# JCarlos_e_Renato.net
KiCad netlist of a schematic drawn in EAGLE
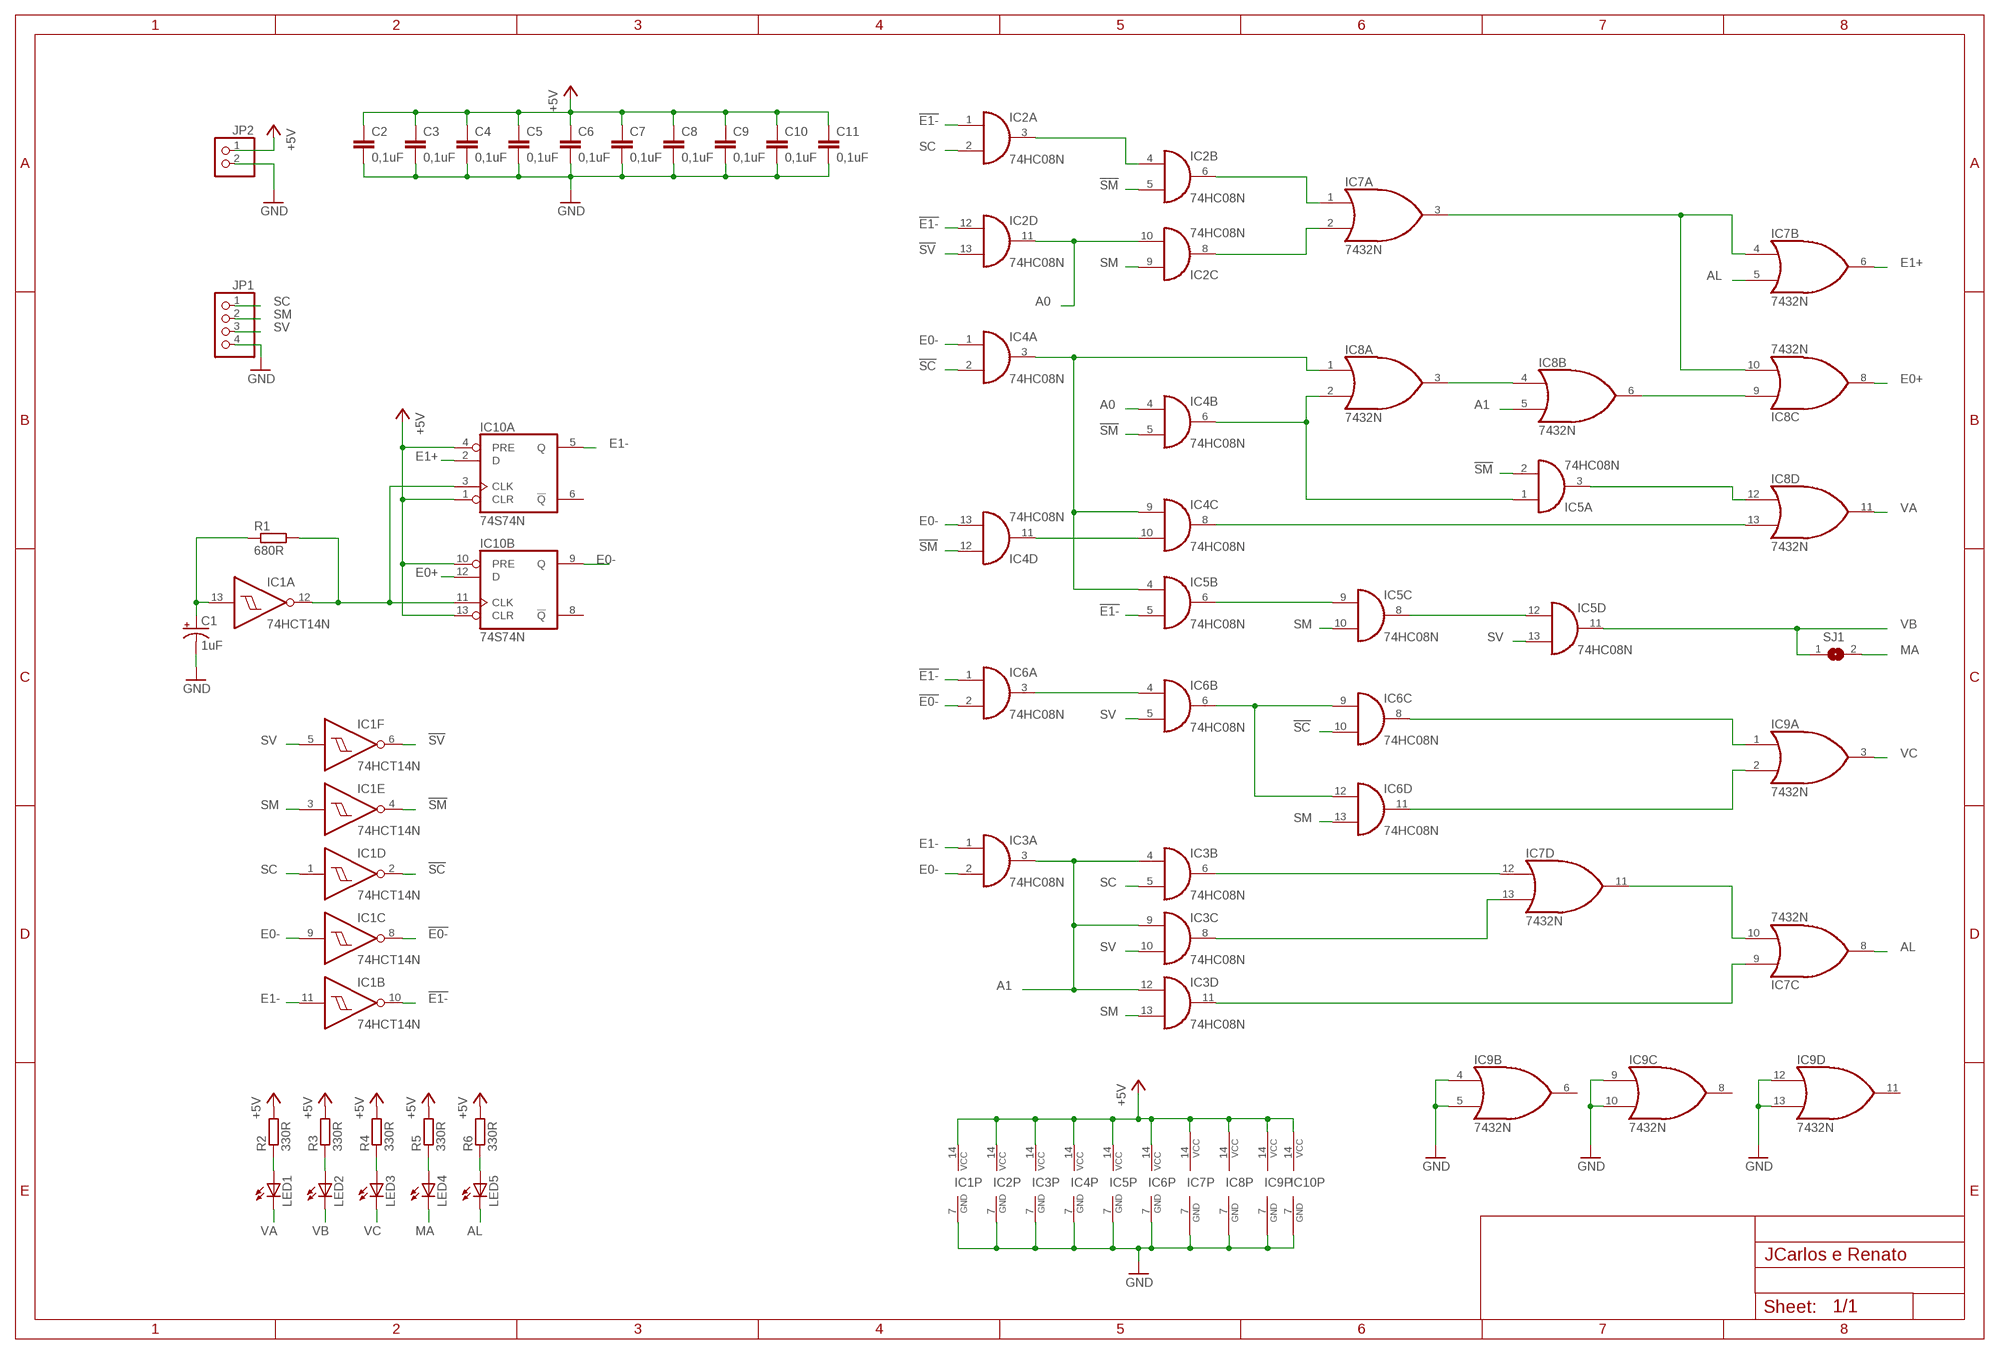
[diagram p0: schematic, sheet 1]

(export (version "E")
  (design (tool "Eeschema 10.0.6"))
  (components
    (comp (ref "C1")
      (value "1uF")
      (footprint "eagle-import:E5-6")
      (libsource (lib "eagle-import") (part "CPOL-USE5-6"))
    )
    (comp (ref "C2")
      (value "0,1uF")
      (footprint "eagle-import:C050-025X075")
      (libsource (lib "eagle-import") (part "C-EU050-025X075"))
    )
    (comp (ref "C3")
      (value "0,1uF")
      (footprint "eagle-import:C050-025X075")
      (libsource (lib "eagle-import") (part "C-EU050-025X075"))
    )
    (comp (ref "C4")
      (value "0,1uF")
      (footprint "eagle-import:C050-025X075")
      (libsource (lib "eagle-import") (part "C-EU050-025X075"))
    )
    (comp (ref "C5")
      (value "0,1uF")
      (footprint "eagle-import:C050-025X075")
      (libsource (lib "eagle-import") (part "C-EU050-025X075"))
    )
    (comp (ref "C6")
      (value "0,1uF")
      (footprint "eagle-import:C050-025X075")
      (libsource (lib "eagle-import") (part "C-EU050-025X075"))
    )
    (comp (ref "C7")
      (value "0,1uF")
      (footprint "eagle-import:C050-025X075")
      (libsource (lib "eagle-import") (part "C-EU050-025X075"))
    )
    (comp (ref "C8")
      (value "0,1uF")
      (footprint "eagle-import:C050-025X075")
      (libsource (lib "eagle-import") (part "C-EU050-025X075"))
    )
    (comp (ref "C9")
      (value "0,1uF")
      (footprint "eagle-import:C050-025X075")
      (libsource (lib "eagle-import") (part "C-EU050-025X075"))
    )
    (comp (ref "C10")
      (value "0,1uF")
      (footprint "eagle-import:C050-025X075")
      (libsource (lib "eagle-import") (part "C-EU050-025X075"))
    )
    (comp (ref "C11")
      (value "0,1uF")
      (footprint "eagle-import:C050-025X075")
      (libsource (lib "eagle-import") (part "C-EU050-025X075"))
    )
    (comp (ref "IC1")
      (value "74HCT14N")
      (footprint "eagle-import:DIL14")
      (libsource (lib "eagle-import") (part "7414NHCT"))
    )
    (comp (ref "IC2")
      (value "74HC08N")
      (footprint "eagle-import:DIL14")
      (libsource (lib "eagle-import") (part "7408NHC"))
    )
    (comp (ref "IC3")
      (value "74HC08N")
      (footprint "eagle-import:DIL14")
      (libsource (lib "eagle-import") (part "7408NHC"))
    )
    (comp (ref "IC4")
      (value "74HC08N")
      (footprint "eagle-import:DIL14")
      (libsource (lib "eagle-import") (part "7408NHC"))
    )
    (comp (ref "IC5")
      (value "74HC08N")
      (footprint "eagle-import:DIL14")
      (libsource (lib "eagle-import") (part "7408NHC"))
    )
    (comp (ref "IC6")
      (value "74HC08N")
      (footprint "eagle-import:DIL14")
      (libsource (lib "eagle-import") (part "7408NHC"))
    )
    (comp (ref "IC7")
      (value "7432N")
      (footprint "eagle-import:DIL14")
      (libsource (lib "eagle-import") (part "7432N"))
    )
    (comp (ref "IC8")
      (value "7432N")
      (footprint "eagle-import:DIL14")
      (libsource (lib "eagle-import") (part "7432N"))
    )
    (comp (ref "IC9")
      (value "7432N")
      (footprint "eagle-import:DIL14")
      (libsource (lib "eagle-import") (part "7432N"))
    )
    (comp (ref "IC10")
      (value "74S74N")
      (footprint "eagle-import:DIL14")
      (libsource (lib "eagle-import") (part "7474NS"))
    )
    (comp (ref "JP1")
      (value "PINHD-1X4")
      (footprint "eagle-import:1X04")
      (libsource (lib "eagle-import") (part "PINHD-1X4"))
    )
    (comp (ref "JP2")
      (value "PINHD-1X2")
      (footprint "eagle-import:1X02")
      (libsource (lib "eagle-import") (part "PINHD-1X2"))
    )
    (comp (ref "LED1")
      (value "LED5MM")
      (footprint "eagle-import:LED5MM")
      (libsource (lib "eagle-import") (part "LED5MM"))
    )
    (comp (ref "LED2")
      (value "LED5MM")
      (footprint "eagle-import:LED5MM")
      (libsource (lib "eagle-import") (part "LED5MM"))
    )
    (comp (ref "LED3")
      (value "LED5MM")
      (footprint "eagle-import:LED5MM")
      (libsource (lib "eagle-import") (part "LED5MM"))
    )
    (comp (ref "LED4")
      (value "LED5MM")
      (footprint "eagle-import:LED5MM")
      (libsource (lib "eagle-import") (part "LED5MM"))
    )
    (comp (ref "LED5")
      (value "LED5MM")
      (footprint "eagle-import:LED5MM")
      (libsource (lib "eagle-import") (part "LED5MM"))
    )
    (comp (ref "R1")
      (value "680R")
      (footprint "eagle-import:0204_5")
      (libsource (lib "eagle-import") (part "R-EU_0204/5"))
    )
    (comp (ref "R2")
      (value "330R")
      (footprint "eagle-import:0207_10")
      (libsource (lib "eagle-import") (part "R-EU_0207/10"))
    )
    (comp (ref "R3")
      (value "330R")
      (footprint "eagle-import:0207_10")
      (libsource (lib "eagle-import") (part "R-EU_0207/10"))
    )
    (comp (ref "R4")
      (value "330R")
      (footprint "eagle-import:0207_10")
      (libsource (lib "eagle-import") (part "R-EU_0207/10"))
    )
    (comp (ref "R5")
      (value "330R")
      (footprint "eagle-import:0207_10")
      (libsource (lib "eagle-import") (part "R-EU_0207/10"))
    )
    (comp (ref "R6")
      (value "330R")
      (footprint "eagle-import:0207_10")
      (libsource (lib "eagle-import") (part "R-EU_0207/10"))
    )
    (comp (ref "SJ1") (value "SJ") (footprint "eagle-import:SJ") (libsource (lib "eagle-import") (part "SJ")))
  )
  (nets
    (net (code "1") (name "+5V") (class "Default")
      (node (ref "C10") (pin "1") (pinfunction "1_1") (pintype "passive"))
      (node (ref "C11") (pin "1") (pinfunction "1_1") (pintype "passive"))
      (node (ref "C2") (pin "1") (pinfunction "1_1") (pintype "passive"))
      (node (ref "C3") (pin "1") (pinfunction "1_1") (pintype "passive"))
      (node (ref "C4") (pin "1") (pinfunction "1_1") (pintype "passive"))
      (node (ref "C5") (pin "1") (pinfunction "1_1") (pintype "passive"))
      (node (ref "C6") (pin "1") (pinfunction "1_1") (pintype "passive"))
      (node (ref "C7") (pin "1") (pinfunction "1_1") (pintype "passive"))
      (node (ref "C8") (pin "1") (pinfunction "1_1") (pintype "passive"))
      (node (ref "C9") (pin "1") (pinfunction "1_1") (pintype "passive"))
      (node (ref "IC1") (pin "14") (pinfunction "VCC_14") (pintype "power_in"))
      (node (ref "IC10") (pin "1") (pinfunction "CLR_1") (pintype "input"))
      (node (ref "IC10") (pin "10") (pinfunction "PRE_10") (pintype "input"))
      (node (ref "IC10") (pin "13") (pinfunction "CLR_13") (pintype "input"))
      (node (ref "IC10") (pin "14") (pinfunction "VCC_14") (pintype "power_in"))
      (node (ref "IC10") (pin "4") (pinfunction "PRE_4") (pintype "input"))
      (node (ref "IC2") (pin "14") (pinfunction "VCC_14") (pintype "power_in"))
      (node (ref "IC3") (pin "14") (pinfunction "VCC_14") (pintype "power_in"))
      (node (ref "IC4") (pin "14") (pinfunction "VCC_14") (pintype "power_in"))
      (node (ref "IC5") (pin "14") (pinfunction "VCC_14") (pintype "power_in"))
      (node (ref "IC6") (pin "14") (pinfunction "VCC_14") (pintype "power_in"))
      (node (ref "IC7") (pin "14") (pinfunction "VCC_14") (pintype "power_in"))
      (node (ref "IC8") (pin "14") (pinfunction "VCC_14") (pintype "power_in"))
      (node (ref "IC9") (pin "14") (pinfunction "VCC_14") (pintype "power_in"))
      (node (ref "JP2") (pin "1") (pinfunction "1_1") (pintype "passive"))
      (node (ref "R2") (pin "2") (pinfunction "2_2") (pintype "passive"))
      (node (ref "R3") (pin "2") (pinfunction "2_2") (pintype "passive"))
      (node (ref "R4") (pin "2") (pinfunction "2_2") (pintype "passive"))
      (node (ref "R5") (pin "2") (pinfunction "2_2") (pintype "passive"))
      (node (ref "R6") (pin "2") (pinfunction "2_2") (pintype "passive"))
    )
    (net (code "2") (name "/A0") (class "Default")
      (node (ref "IC2") (pin "10") (pinfunction "I1_10") (pintype "input"))
      (node (ref "IC2") (pin "11") (pinfunction "O_11") (pintype "output"))
      (node (ref "IC4") (pin "4") (pinfunction "I0_4") (pintype "input"))
    )
    (net (code "3") (name "/A1") (class "Default")
      (node (ref "IC3") (pin "12") (pinfunction "I0_12") (pintype "input"))
      (node (ref "IC3") (pin "3") (pinfunction "O_3") (pintype "output"))
      (node (ref "IC3") (pin "4") (pinfunction "I0_4") (pintype "input"))
      (node (ref "IC3") (pin "9") (pinfunction "I0_9") (pintype "input"))
      (node (ref "IC8") (pin "5") (pinfunction "I1_5") (pintype "input"))
    )
    (net (code "4") (name "/AL") (class "Default")
      (node (ref "IC7") (pin "5") (pinfunction "I1_5") (pintype "input"))
      (node (ref "IC7") (pin "8") (pinfunction "O_8") (pintype "output"))
      (node (ref "LED5") (pin "K") (pinfunction "C_K") (pintype "passive"))
    )
    (net (code "5") (name "/E0+") (class "Default")
      (node (ref "IC10") (pin "12") (pinfunction "D_12") (pintype "input"))
      (node (ref "IC8") (pin "8") (pinfunction "O_8") (pintype "output"))
    )
    (net (code "6") (name "/E0-") (class "Default")
      (node (ref "IC1") (pin "9") (pinfunction "I_9") (pintype "input"))
      (node (ref "IC10") (pin "9") (pinfunction "Q_9") (pintype "output"))
      (node (ref "IC3") (pin "2") (pinfunction "I1_2") (pintype "input"))
      (node (ref "IC4") (pin "1") (pinfunction "I0_1") (pintype "input"))
      (node (ref "IC4") (pin "13") (pinfunction "I1_13") (pintype "input"))
    )
    (net (code "7") (name "/E1+") (class "Default")
      (node (ref "IC10") (pin "2") (pinfunction "D_2") (pintype "input"))
      (node (ref "IC7") (pin "6") (pinfunction "O_6") (pintype "output"))
    )
    (net (code "8") (name "/E1-") (class "Default")
      (node (ref "IC1") (pin "11") (pinfunction "I_11") (pintype "input"))
      (node (ref "IC10") (pin "5") (pinfunction "Q_5") (pintype "output"))
      (node (ref "IC3") (pin "1") (pinfunction "I0_1") (pintype "input"))
    )
    (net (code "9") (name "/MA") (class "Default")
      (node (ref "LED4") (pin "K") (pinfunction "C_K") (pintype "passive"))
      (node (ref "SJ1") (pin "2") (pinfunction "2_2") (pintype "passive"))
    )
    (net (code "10") (name "/SC") (class "Default")
      (node (ref "IC1") (pin "1") (pinfunction "I_1") (pintype "input"))
      (node (ref "IC2") (pin "2") (pinfunction "I1_2") (pintype "input"))
      (node (ref "IC3") (pin "5") (pinfunction "I1_5") (pintype "input"))
      (node (ref "JP1") (pin "1") (pinfunction "1_1") (pintype "passive"))
    )
    (net (code "11") (name "/SM") (class "Default")
      (node (ref "IC1") (pin "3") (pinfunction "I_3") (pintype "input"))
      (node (ref "IC2") (pin "9") (pinfunction "I0_9") (pintype "input"))
      (node (ref "IC3") (pin "13") (pinfunction "I1_13") (pintype "input"))
      (node (ref "IC5") (pin "10") (pinfunction "I1_10") (pintype "input"))
      (node (ref "IC6") (pin "13") (pinfunction "I1_13") (pintype "input"))
      (node (ref "JP1") (pin "2") (pinfunction "2_2") (pintype "passive"))
    )
    (net (code "12") (name "/SV") (class "Default")
      (node (ref "IC1") (pin "5") (pinfunction "I_5") (pintype "input"))
      (node (ref "IC3") (pin "10") (pinfunction "I1_10") (pintype "input"))
      (node (ref "IC5") (pin "13") (pinfunction "I1_13") (pintype "input"))
      (node (ref "IC6") (pin "5") (pinfunction "I1_5") (pintype "input"))
      (node (ref "JP1") (pin "3") (pinfunction "3_3") (pintype "passive"))
    )
    (net (code "13") (name "/VA") (class "Default")
      (node (ref "IC8") (pin "11") (pinfunction "O_11") (pintype "output"))
      (node (ref "LED1") (pin "K") (pinfunction "C_K") (pintype "passive"))
    )
    (net (code "14") (name "/VB") (class "Default")
      (node (ref "IC5") (pin "11") (pinfunction "O_11") (pintype "output"))
      (node (ref "LED2") (pin "K") (pinfunction "C_K") (pintype "passive"))
      (node (ref "SJ1") (pin "1") (pinfunction "1_1") (pintype "passive"))
    )
    (net (code "15") (name "/VC") (class "Default")
      (node (ref "IC9") (pin "3") (pinfunction "O_3") (pintype "output"))
      (node (ref "LED3") (pin "K") (pinfunction "C_K") (pintype "passive"))
    )
    (net (code "16") (name "/~{E0-}") (class "Default")
      (node (ref "IC1") (pin "8") (pinfunction "O_8") (pintype "output"))
      (node (ref "IC6") (pin "2") (pinfunction "I1_2") (pintype "input"))
    )
    (net (code "17") (name "/~{E1-}") (class "Default")
      (node (ref "IC1") (pin "10") (pinfunction "O_10") (pintype "output"))
      (node (ref "IC2") (pin "1") (pinfunction "I0_1") (pintype "input"))
      (node (ref "IC2") (pin "12") (pinfunction "I0_12") (pintype "input"))
      (node (ref "IC5") (pin "5") (pinfunction "I1_5") (pintype "input"))
      (node (ref "IC6") (pin "1") (pinfunction "I0_1") (pintype "input"))
    )
    (net (code "18") (name "/~{SC}") (class "Default")
      (node (ref "IC1") (pin "2") (pinfunction "O_2") (pintype "output"))
      (node (ref "IC4") (pin "2") (pinfunction "I1_2") (pintype "input"))
      (node (ref "IC6") (pin "10") (pinfunction "I1_10") (pintype "input"))
    )
    (net (code "19") (name "/~{SM}") (class "Default")
      (node (ref "IC1") (pin "4") (pinfunction "O_4") (pintype "output"))
      (node (ref "IC2") (pin "5") (pinfunction "I1_5") (pintype "input"))
      (node (ref "IC4") (pin "12") (pinfunction "I0_12") (pintype "input"))
      (node (ref "IC4") (pin "5") (pinfunction "I1_5") (pintype "input"))
      (node (ref "IC5") (pin "2") (pinfunction "I1_2") (pintype "input"))
    )
    (net (code "20") (name "/~{SV}") (class "Default")
      (node (ref "IC1") (pin "6") (pinfunction "O_6") (pintype "output"))
      (node (ref "IC2") (pin "13") (pinfunction "I1_13") (pintype "input"))
    )
    (net (code "21") (name "GND") (class "Default")
      (node (ref "C1") (pin "-") (pinfunction "-_-") (pintype "passive"))
      (node (ref "C10") (pin "2") (pinfunction "2_2") (pintype "passive"))
      (node (ref "C11") (pin "2") (pinfunction "2_2") (pintype "passive"))
      (node (ref "C2") (pin "2") (pinfunction "2_2") (pintype "passive"))
      (node (ref "C3") (pin "2") (pinfunction "2_2") (pintype "passive"))
      (node (ref "C4") (pin "2") (pinfunction "2_2") (pintype "passive"))
      (node (ref "C5") (pin "2") (pinfunction "2_2") (pintype "passive"))
      (node (ref "C6") (pin "2") (pinfunction "2_2") (pintype "passive"))
      (node (ref "C7") (pin "2") (pinfunction "2_2") (pintype "passive"))
      (node (ref "C8") (pin "2") (pinfunction "2_2") (pintype "passive"))
      (node (ref "C9") (pin "2") (pinfunction "2_2") (pintype "passive"))
      (node (ref "IC1") (pin "7") (pinfunction "GND_7") (pintype "power_in"))
      (node (ref "IC10") (pin "7") (pinfunction "GND_7") (pintype "power_in"))
      (node (ref "IC2") (pin "7") (pinfunction "GND_7") (pintype "power_in"))
      (node (ref "IC3") (pin "7") (pinfunction "GND_7") (pintype "power_in"))
      (node (ref "IC4") (pin "7") (pinfunction "GND_7") (pintype "power_in"))
      (node (ref "IC5") (pin "7") (pinfunction "GND_7") (pintype "power_in"))
      (node (ref "IC6") (pin "7") (pinfunction "GND_7") (pintype "power_in"))
      (node (ref "IC7") (pin "7") (pinfunction "GND_7") (pintype "power_in"))
      (node (ref "IC8") (pin "7") (pinfunction "GND_7") (pintype "power_in"))
      (node (ref "IC9") (pin "10") (pinfunction "I1_10") (pintype "input"))
      (node (ref "IC9") (pin "12") (pinfunction "I0_12") (pintype "input"))
      (node (ref "IC9") (pin "13") (pinfunction "I1_13") (pintype "input"))
      (node (ref "IC9") (pin "4") (pinfunction "I0_4") (pintype "input"))
      (node (ref "IC9") (pin "5") (pinfunction "I1_5") (pintype "input"))
      (node (ref "IC9") (pin "7") (pinfunction "GND_7") (pintype "power_in"))
      (node (ref "IC9") (pin "9") (pinfunction "I0_9") (pintype "input"))
      (node (ref "JP1") (pin "4") (pinfunction "4_4") (pintype "passive"))
      (node (ref "JP2") (pin "2") (pinfunction "2_2") (pintype "passive"))
    )
    (net (code "22") (name "Net-(IC1A-I)") (class "Default")
      (node (ref "C1") (pin "+") (pinfunction "+_+") (pintype "passive"))
      (node (ref "IC1") (pin "13") (pinfunction "I_13") (pintype "input"))
      (node (ref "R1") (pin "1") (pinfunction "1_1") (pintype "passive"))
    )
    (net (code "23") (name "Net-(IC2A-O)") (class "Default")
      (node (ref "IC2") (pin "3") (pinfunction "O_3") (pintype "output"))
      (node (ref "IC2") (pin "4") (pinfunction "I0_4") (pintype "input"))
    )
    (net (code "24") (name "Net-(IC2B-O)") (class "Default")
      (node (ref "IC2") (pin "6") (pinfunction "O_6") (pintype "output"))
      (node (ref "IC7") (pin "1") (pinfunction "I0_1") (pintype "input"))
    )
    (net (code "25") (name "Net-(IC2C-O)") (class "Default")
      (node (ref "IC2") (pin "8") (pinfunction "O_8") (pintype "output"))
      (node (ref "IC7") (pin "2") (pinfunction "I1_2") (pintype "input"))
    )
    (net (code "26") (name "Net-(IC3B-O)") (class "Default")
      (node (ref "IC3") (pin "6") (pinfunction "O_6") (pintype "output"))
      (node (ref "IC7") (pin "12") (pinfunction "I0_12") (pintype "input"))
    )
    (net (code "27") (name "Net-(IC3C-O)") (class "Default")
      (node (ref "IC3") (pin "8") (pinfunction "O_8") (pintype "output"))
      (node (ref "IC7") (pin "13") (pinfunction "I1_13") (pintype "input"))
    )
    (net (code "28") (name "Net-(IC3D-O)") (class "Default")
      (node (ref "IC3") (pin "11") (pinfunction "O_11") (pintype "output"))
      (node (ref "IC7") (pin "9") (pinfunction "I0_9") (pintype "input"))
    )
    (net (code "29") (name "Net-(IC4A-O)") (class "Default")
      (node (ref "IC4") (pin "3") (pinfunction "O_3") (pintype "output"))
      (node (ref "IC4") (pin "9") (pinfunction "I0_9") (pintype "input"))
      (node (ref "IC5") (pin "4") (pinfunction "I0_4") (pintype "input"))
      (node (ref "IC8") (pin "1") (pinfunction "I0_1") (pintype "input"))
    )
    (net (code "30") (name "Net-(IC4B-O)") (class "Default")
      (node (ref "IC4") (pin "6") (pinfunction "O_6") (pintype "output"))
      (node (ref "IC5") (pin "1") (pinfunction "I0_1") (pintype "input"))
      (node (ref "IC8") (pin "2") (pinfunction "I1_2") (pintype "input"))
    )
    (net (code "31") (name "Net-(IC4C-I1)") (class "Default")
      (node (ref "IC4") (pin "10") (pinfunction "I1_10") (pintype "input"))
      (node (ref "IC4") (pin "11") (pinfunction "O_11") (pintype "output"))
    )
    (net (code "32") (name "Net-(IC4C-O)") (class "Default")
      (node (ref "IC4") (pin "8") (pinfunction "O_8") (pintype "output"))
      (node (ref "IC8") (pin "13") (pinfunction "I1_13") (pintype "input"))
    )
    (net (code "33") (name "Net-(IC5A-O)") (class "Default")
      (node (ref "IC5") (pin "3") (pinfunction "O_3") (pintype "output"))
      (node (ref "IC8") (pin "12") (pinfunction "I0_12") (pintype "input"))
    )
    (net (code "34") (name "Net-(IC5B-O)") (class "Default")
      (node (ref "IC5") (pin "6") (pinfunction "O_6") (pintype "output"))
      (node (ref "IC5") (pin "9") (pinfunction "I0_9") (pintype "input"))
    )
    (net (code "35") (name "Net-(IC5C-O)") (class "Default")
      (node (ref "IC5") (pin "12") (pinfunction "I0_12") (pintype "input"))
      (node (ref "IC5") (pin "8") (pinfunction "O_8") (pintype "output"))
    )
    (net (code "36") (name "Net-(IC6A-O)") (class "Default")
      (node (ref "IC6") (pin "3") (pinfunction "O_3") (pintype "output"))
      (node (ref "IC6") (pin "4") (pinfunction "I0_4") (pintype "input"))
    )
    (net (code "37") (name "Net-(IC6B-O)") (class "Default")
      (node (ref "IC6") (pin "12") (pinfunction "I0_12") (pintype "input"))
      (node (ref "IC6") (pin "6") (pinfunction "O_6") (pintype "output"))
      (node (ref "IC6") (pin "9") (pinfunction "I0_9") (pintype "input"))
    )
    (net (code "38") (name "Net-(IC6C-O)") (class "Default")
      (node (ref "IC6") (pin "8") (pinfunction "O_8") (pintype "output"))
      (node (ref "IC9") (pin "1") (pinfunction "I0_1") (pintype "input"))
    )
    (net (code "39") (name "Net-(IC6D-O)") (class "Default")
      (node (ref "IC6") (pin "11") (pinfunction "O_11") (pintype "output"))
      (node (ref "IC9") (pin "2") (pinfunction "I1_2") (pintype "input"))
    )
    (net (code "40") (name "Net-(IC7A-O)") (class "Default")
      (node (ref "IC7") (pin "3") (pinfunction "O_3") (pintype "output"))
      (node (ref "IC7") (pin "4") (pinfunction "I0_4") (pintype "input"))
      (node (ref "IC8") (pin "10") (pinfunction "I1_10") (pintype "input"))
    )
    (net (code "41") (name "Net-(IC7C-I1)") (class "Default")
      (node (ref "IC7") (pin "10") (pinfunction "I1_10") (pintype "input"))
      (node (ref "IC7") (pin "11") (pinfunction "O_11") (pintype "output"))
    )
    (net (code "42") (name "Net-(IC8A-O)") (class "Default")
      (node (ref "IC8") (pin "3") (pinfunction "O_3") (pintype "output"))
      (node (ref "IC8") (pin "4") (pinfunction "I0_4") (pintype "input"))
    )
    (net (code "43") (name "Net-(IC8B-O)") (class "Default")
      (node (ref "IC8") (pin "6") (pinfunction "O_6") (pintype "output"))
      (node (ref "IC8") (pin "9") (pinfunction "I0_9") (pintype "input"))
    )
    (net (code "44") (name "Net-(IC10A-CLK)") (class "Default")
      (node (ref "IC1") (pin "12") (pinfunction "O_12") (pintype "output"))
      (node (ref "IC10") (pin "11") (pinfunction "CLK_11") (pintype "input"))
      (node (ref "IC10") (pin "3") (pinfunction "CLK_3") (pintype "input"))
      (node (ref "R1") (pin "2") (pinfunction "2_2") (pintype "passive"))
    )
    (net (code "45") (name "Net-(LED1-PadA)") (class "Default")
      (node (ref "LED1") (pin "A") (pinfunction "A_A") (pintype "passive"))
      (node (ref "R2") (pin "1") (pinfunction "1_1") (pintype "passive"))
    )
    (net (code "46") (name "Net-(LED2-PadA)") (class "Default")
      (node (ref "LED2") (pin "A") (pinfunction "A_A") (pintype "passive"))
      (node (ref "R3") (pin "1") (pinfunction "1_1") (pintype "passive"))
    )
    (net (code "47") (name "Net-(LED3-PadA)") (class "Default")
      (node (ref "LED3") (pin "A") (pinfunction "A_A") (pintype "passive"))
      (node (ref "R4") (pin "1") (pinfunction "1_1") (pintype "passive"))
    )
    (net (code "48") (name "Net-(LED4-PadA)") (class "Default")
      (node (ref "LED4") (pin "A") (pinfunction "A_A") (pintype "passive"))
      (node (ref "R5") (pin "1") (pinfunction "1_1") (pintype "passive"))
    )
    (net (code "49") (name "Net-(LED5-PadA)") (class "Default")
      (node (ref "LED5") (pin "A") (pinfunction "A_A") (pintype "passive"))
      (node (ref "R6") (pin "1") (pinfunction "1_1") (pintype "passive"))
    )
    (net (code "50") (name "unconnected-(IC9B-O-Pad6)") (class "Default")
      (node (ref "IC9") (pin "6") (pinfunction "O_6") (pintype "output"))
    )
    (net (code "51") (name "unconnected-(IC9C-O-Pad8)") (class "Default")
      (node (ref "IC9") (pin "8") (pinfunction "O_8") (pintype "output"))
    )
    (net (code "52") (name "unconnected-(IC9D-O-Pad11)") (class "Default")
      (node (ref "IC9") (pin "11") (pinfunction "O_11") (pintype "output"))
    )
    (net (code "53") (name "unconnected-(IC10A-~{Q}-Pad6)") (class "Default")
      (node (ref "IC10") (pin "6") (pinfunction "~{Q}_6") (pintype "output"))
    )
    (net (code "54") (name "unconnected-(IC10B-~{Q}-Pad8)") (class "Default")
      (node (ref "IC10") (pin "8") (pinfunction "~{Q}_8") (pintype "output"))
    )
  )
)
